# Xiaoyun2333_CH340-USB-Downloader__hardwa.net
KiCad netlist of a schematic drawn in Altium Designer
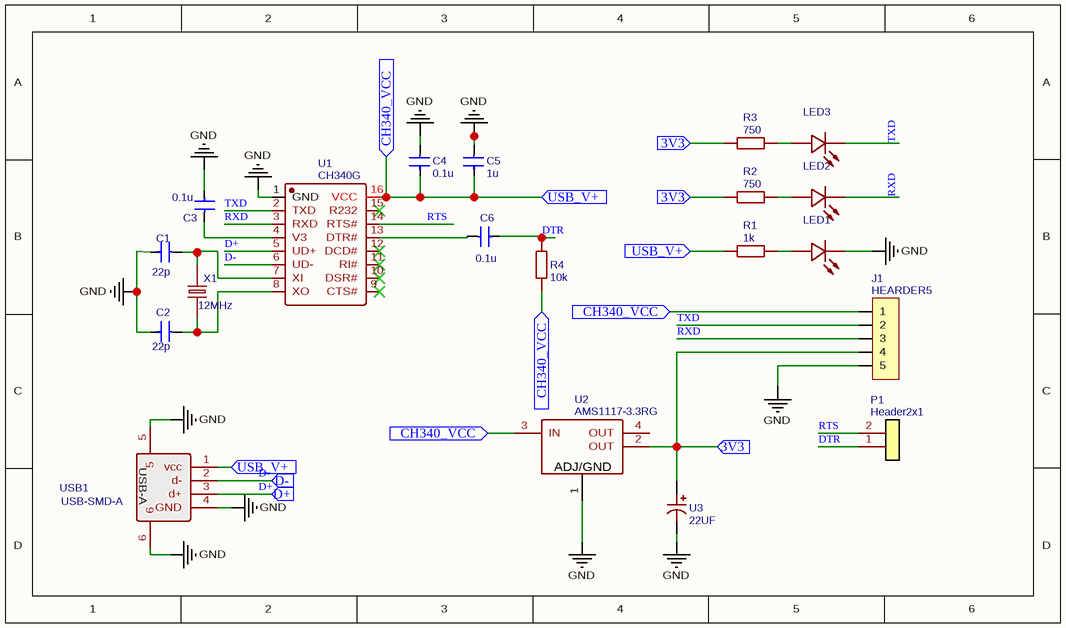
[diagram p0: Xiaoyun2333_CH340-USB-Downloader__hardware__ch340.schdoc]

(export (version "E")
  (design (tool "Eeschema 10.0.6"))
  (components
    (comp (ref "C1")
      (value "22p")
      (fields (field (name "CONTRIBUTOR") "gaoziting"))
      (libsource (lib "altium-import") (part "root_1_22p_"))
    )
    (comp (ref "C2")
      (value "22p")
      (fields (field (name "CONTRIBUTOR") "gaoziting"))
      (libsource (lib "altium-import") (part "root_1_22p_"))
    )
    (comp (ref "C3")
      (value "0.1u")
      (fields (field (name "CONTRIBUTOR") "gaoziting"))
      (libsource (lib "altium-import") (part "root_0_0.1u_"))
    )
    (comp (ref "C4")
      (value "0.1u")
      (fields (field (name "CONTRIBUTOR") "gaoziting"))
      (libsource (lib "altium-import") (part "root_2_0.1u_"))
    )
    (comp (ref "C5")
      (value "1u")
      (fields (field (name "CONTRIBUTOR") "gaoziting"))
      (libsource (lib "altium-import") (part "root_2_1u_"))
    )
    (comp (ref "C6")
      (value "0.1u")
      (fields (field (name "CONTRIBUTOR") "gaoziting"))
      (libsource (lib "altium-import") (part "root_3_0.1u_"))
    )
    (comp (ref "J1")
      (value "HEARDER5")
      (fields (field (name "CONTRIBUTOR") "lhl234"))
      (libsource (lib "altium-import") (part "root_0_HEARDER5_"))
    )
    (comp (ref "LED1")
      (value "LED0805")
      (fields
        (field (name "BOM_SUPPLIER PART") "C9900012722")
        (field (name "BOM_MANUFACTURER PART") "led0805")
        (field (name "CONTRIBUTOR") "LCSC")
      )
      (libsource (lib "altium-import") (part "root_2_LED0805_"))
    )
    (comp (ref "LED2")
      (value "LED0805")
      (fields
        (field (name "BOM_SUPPLIER PART") "C9900012722")
        (field (name "BOM_MANUFACTURER PART") "led0805")
        (field (name "CONTRIBUTOR") "LCSC")
      )
      (libsource (lib "altium-import") (part "root_2_LED0805_"))
    )
    (comp (ref "LED3")
      (value "LED0805")
      (fields
        (field (name "BOM_SUPPLIER PART") "C9900012722")
        (field (name "BOM_MANUFACTURER PART") "led0805")
        (field (name "CONTRIBUTOR") "LCSC")
      )
      (libsource (lib "altium-import") (part "root_2_LED0805_"))
    )
    (comp (ref "P1")
      (value "Header2x1")
      (fields (field (name "CONTRIBUTOR") "RenWL"))
      (libsource (lib "altium-import") (part "root_2_Header2x1_"))
    )
    (comp (ref "R1")
      (value "1k")
      (fields
        (field (name "BOM_SUPPLIER PART") "C9900012715")
        (field (name "BOM_MANUFACTURER PART") "0805")
        (field (name "CONTRIBUTOR") "LCSC")
      )
      (libsource (lib "altium-import") (part "root_2_1k_"))
    )
    (comp (ref "R2")
      (value "750")
      (fields
        (field (name "BOM_SUPPLIER PART") "C9900012715")
        (field (name "BOM_MANUFACTURER PART") "0805")
        (field (name "CONTRIBUTOR") "LCSC")
      )
      (libsource (lib "altium-import") (part "root_2_750_"))
    )
    (comp (ref "R3")
      (value "750")
      (fields
        (field (name "BOM_SUPPLIER PART") "C9900012715")
        (field (name "BOM_MANUFACTURER PART") "0805")
        (field (name "CONTRIBUTOR") "LCSC")
      )
      (libsource (lib "altium-import") (part "root_2_750_"))
    )
    (comp (ref "R4")
      (value "10k")
      (fields
        (field (name "BOM_SUPPLIER PART") "C9900012715")
        (field (name "BOM_MANUFACTURER PART") "0805")
        (field (name "CONTRIBUTOR") "LCSC")
      )
      (libsource (lib "altium-import") (part "root_3_10k_"))
    )
    (comp (ref "U1")
      (value "CH340G")
      (fields (field (name "BOM_SUPPLIER PART") "C14267"))
      (libsource (lib "altium-import") (part "root_0_CH340G_"))
    )
    (comp (ref "U2")
      (value "AMS1117-3.3RG")
      (fields (field (name "BOM_SUPPLIER PART") "C2977152") (field (name "CONTRIBUTOR") "lcsc"))
      (libsource (lib "altium-import") (part "root_0_AMS1117-3.3RG_"))
    )
    (comp (ref "U3")
      (value "22UF")
      (fields
        (field (name "BOM_SUPPLIER PART") "C9900004911")
        (field (name "BOM_MANUFACTURER PART") "22uF/10V,±10%,1206,钽电容")
        (field (name "CONTRIBUTOR") "LCSC")
      )
      (libsource (lib "altium-import") (part "root_3_22UF_"))
    )
    (comp (ref "USB1")
      (value "USB-SMD-A")
      (fields
        (field (name "BOM_MANUFACTURER PART") "U-G-04WS-W-01")
        (field (name "BOM_SUPPLIER PART") "C97324")
      )
      (libsource (lib "altium-import") (part "root_0_USB-SMD-A_"))
    )
    (comp (ref "X1")
      (value "12MHz")
      (fields
        (field (name "BOM_MANUFACTURER PART") "TAXM12M2GLFBET2T")
        (field (name "BOM_SUPPLIER PART") "C111117")
      )
      (libsource (lib "altium-import") (part "root_1_12MHz_"))
    )
  )
  (nets
    (net (code "1") (name "/3V3") (class "Default")
      (node (ref "J1") (pin "4") (pinfunction "4_4") (pintype "passive"))
      (node (ref "R2") (pin "2") (pinfunction "2_2") (pintype "passive"))
      (node (ref "R3") (pin "2") (pinfunction "2_2") (pintype "passive"))
      (node (ref "U2") (pin "2") (pinfunction "OUT_2") (pintype "passive"))
      (node (ref "U3") (pin "1") (pinfunction "1_1") (pintype "passive"))
    )
    (net (code "2") (name "/CH340_VCC") (class "Default")
      (node (ref "C4") (pin "2") (pintype "passive"))
      (node (ref "C5") (pin "2") (pintype "passive"))
      (node (ref "J1") (pin "1") (pinfunction "1_1") (pintype "passive"))
      (node (ref "R1") (pin "2") (pinfunction "2_2") (pintype "passive"))
      (node (ref "R4") (pin "2") (pinfunction "2_2") (pintype "passive"))
      (node (ref "U1") (pin "16") (pinfunction "VCC_16") (pintype "passive"))
      (node (ref "U2") (pin "3") (pinfunction "IN_3") (pintype "passive"))
      (node (ref "USB1") (pin "1") (pinfunction "vcc_1") (pintype "passive"))
    )
    (net (code "3") (name "/D+") (class "Default")
      (node (ref "U1") (pin "5") (pinfunction "UD+_5") (pintype "passive"))
      (node (ref "USB1") (pin "3") (pinfunction "d+_3") (pintype "passive"))
    )
    (net (code "4") (name "/D-") (class "Default")
      (node (ref "U1") (pin "6") (pinfunction "UD-_6") (pintype "passive"))
      (node (ref "USB1") (pin "2") (pinfunction "d-_2") (pintype "passive"))
    )
    (net (code "5") (name "/DTR") (class "Default")
      (node (ref "C6") (pin "2") (pintype "passive"))
      (node (ref "P1") (pin "1") (pinfunction "1_1") (pintype "passive"))
      (node (ref "R4") (pin "1") (pinfunction "1_1") (pintype "passive"))
    )
    (net (code "6") (name "/RTS") (class "Default")
      (node (ref "P1") (pin "2") (pinfunction "2_2") (pintype "passive"))
      (node (ref "U1") (pin "14") (pinfunction "RTS#_14") (pintype "passive"))
    )
    (net (code "7") (name "/RXD") (class "Default")
      (node (ref "J1") (pin "3") (pinfunction "3_3") (pintype "passive"))
      (node (ref "LED2") (pin "1") (pinfunction "-_1") (pintype "passive"))
      (node (ref "U1") (pin "3") (pinfunction "RXD_3") (pintype "passive"))
    )
    (net (code "8") (name "/TXD") (class "Default")
      (node (ref "J1") (pin "2") (pinfunction "2_2") (pintype "passive"))
      (node (ref "LED3") (pin "1") (pinfunction "-_1") (pintype "passive"))
      (node (ref "U1") (pin "2") (pinfunction "TXD_2") (pintype "passive"))
    )
    (net (code "9") (name "GND") (class "Default")
      (node (ref "C1") (pin "2") (pintype "passive"))
      (node (ref "C2") (pin "2") (pintype "passive"))
      (node (ref "C3") (pin "2") (pintype "passive"))
      (node (ref "C4") (pin "1") (pintype "passive"))
      (node (ref "C5") (pin "1") (pintype "passive"))
      (node (ref "J1") (pin "5") (pinfunction "5_5") (pintype "passive"))
      (node (ref "LED1") (pin "1") (pinfunction "-_1") (pintype "passive"))
      (node (ref "U1") (pin "1") (pinfunction "GND_1") (pintype "passive"))
      (node (ref "U2") (pin "1") (pinfunction "ADJ/GND_1") (pintype "passive"))
      (node (ref "U3") (pin "2") (pinfunction "2_2") (pintype "passive"))
      (node (ref "USB1") (pin "4") (pinfunction "GND_4") (pintype "passive"))
      (node (ref "USB1") (pin "5") (pinfunction "5_5") (pintype "passive"))
      (node (ref "USB1") (pin "6") (pinfunction "6_6") (pintype "passive"))
    )
    (net (code "10") (name "Net-(LED1-+)") (class "Default")
      (node (ref "LED1") (pin "2") (pinfunction "+_2") (pintype "passive"))
      (node (ref "R1") (pin "1") (pinfunction "1_1") (pintype "passive"))
    )
    (net (code "11") (name "Net-(LED2-+)") (class "Default")
      (node (ref "LED2") (pin "2") (pinfunction "+_2") (pintype "passive"))
      (node (ref "R2") (pin "1") (pinfunction "1_1") (pintype "passive"))
    )
    (net (code "12") (name "Net-(LED3-+)") (class "Default")
      (node (ref "LED3") (pin "2") (pinfunction "+_2") (pintype "passive"))
      (node (ref "R3") (pin "1") (pinfunction "1_1") (pintype "passive"))
    )
    (net (code "13") (name "Net-(U1-DTR#)") (class "Default")
      (node (ref "C6") (pin "1") (pintype "passive"))
      (node (ref "U1") (pin "13") (pinfunction "DTR#_13") (pintype "passive"))
    )
    (net (code "14") (name "Net-(U1-V3)") (class "Default")
      (node (ref "C3") (pin "1") (pintype "passive"))
      (node (ref "U1") (pin "4") (pinfunction "V3_4") (pintype "passive"))
    )
    (net (code "15") (name "Net-(U1-XI)") (class "Default")
      (node (ref "C1") (pin "1") (pintype "passive"))
      (node (ref "U1") (pin "7") (pinfunction "XI_7") (pintype "passive"))
      (node (ref "X1") (pin "2") (pinfunction "2_2") (pintype "passive"))
    )
    (net (code "16") (name "Net-(U1-XO)") (class "Default")
      (node (ref "C2") (pin "1") (pintype "passive"))
      (node (ref "U1") (pin "8") (pinfunction "XO_8") (pintype "passive"))
      (node (ref "X1") (pin "1") (pinfunction "1_1") (pintype "passive"))
    )
    (net (code "17") (name "unconnected-(U1-CTS#-Pad9)") (class "Default")
      (node (ref "U1") (pin "9") (pinfunction "CTS#_9") (pintype "passive+no_connect"))
    )
    (net (code "18") (name "unconnected-(U1-DCD#-Pad12)") (class "Default")
      (node (ref "U1") (pin "12") (pinfunction "DCD#_12") (pintype "passive+no_connect"))
    )
    (net (code "19") (name "unconnected-(U1-DSR#-Pad10)") (class "Default")
      (node (ref "U1") (pin "10") (pinfunction "DSR#_10") (pintype "passive+no_connect"))
    )
    (net (code "20") (name "unconnected-(U1-R232-Pad15)") (class "Default")
      (node (ref "U1") (pin "15") (pinfunction "R232_15") (pintype "passive+no_connect"))
    )
    (net (code "21") (name "unconnected-(U1-RI#-Pad11)") (class "Default")
      (node (ref "U1") (pin "11") (pinfunction "RI#_11") (pintype "passive+no_connect"))
    )
    (net (code "22") (name "unconnected-(U2-OUT-Pad4)") (class "Default")
      (node (ref "U2") (pin "4") (pinfunction "OUT_4") (pintype "passive"))
    )
  )
)
